# Threeno_DB28_Tx_Rev1.net
KiCad netlist of a schematic drawn in EAGLE
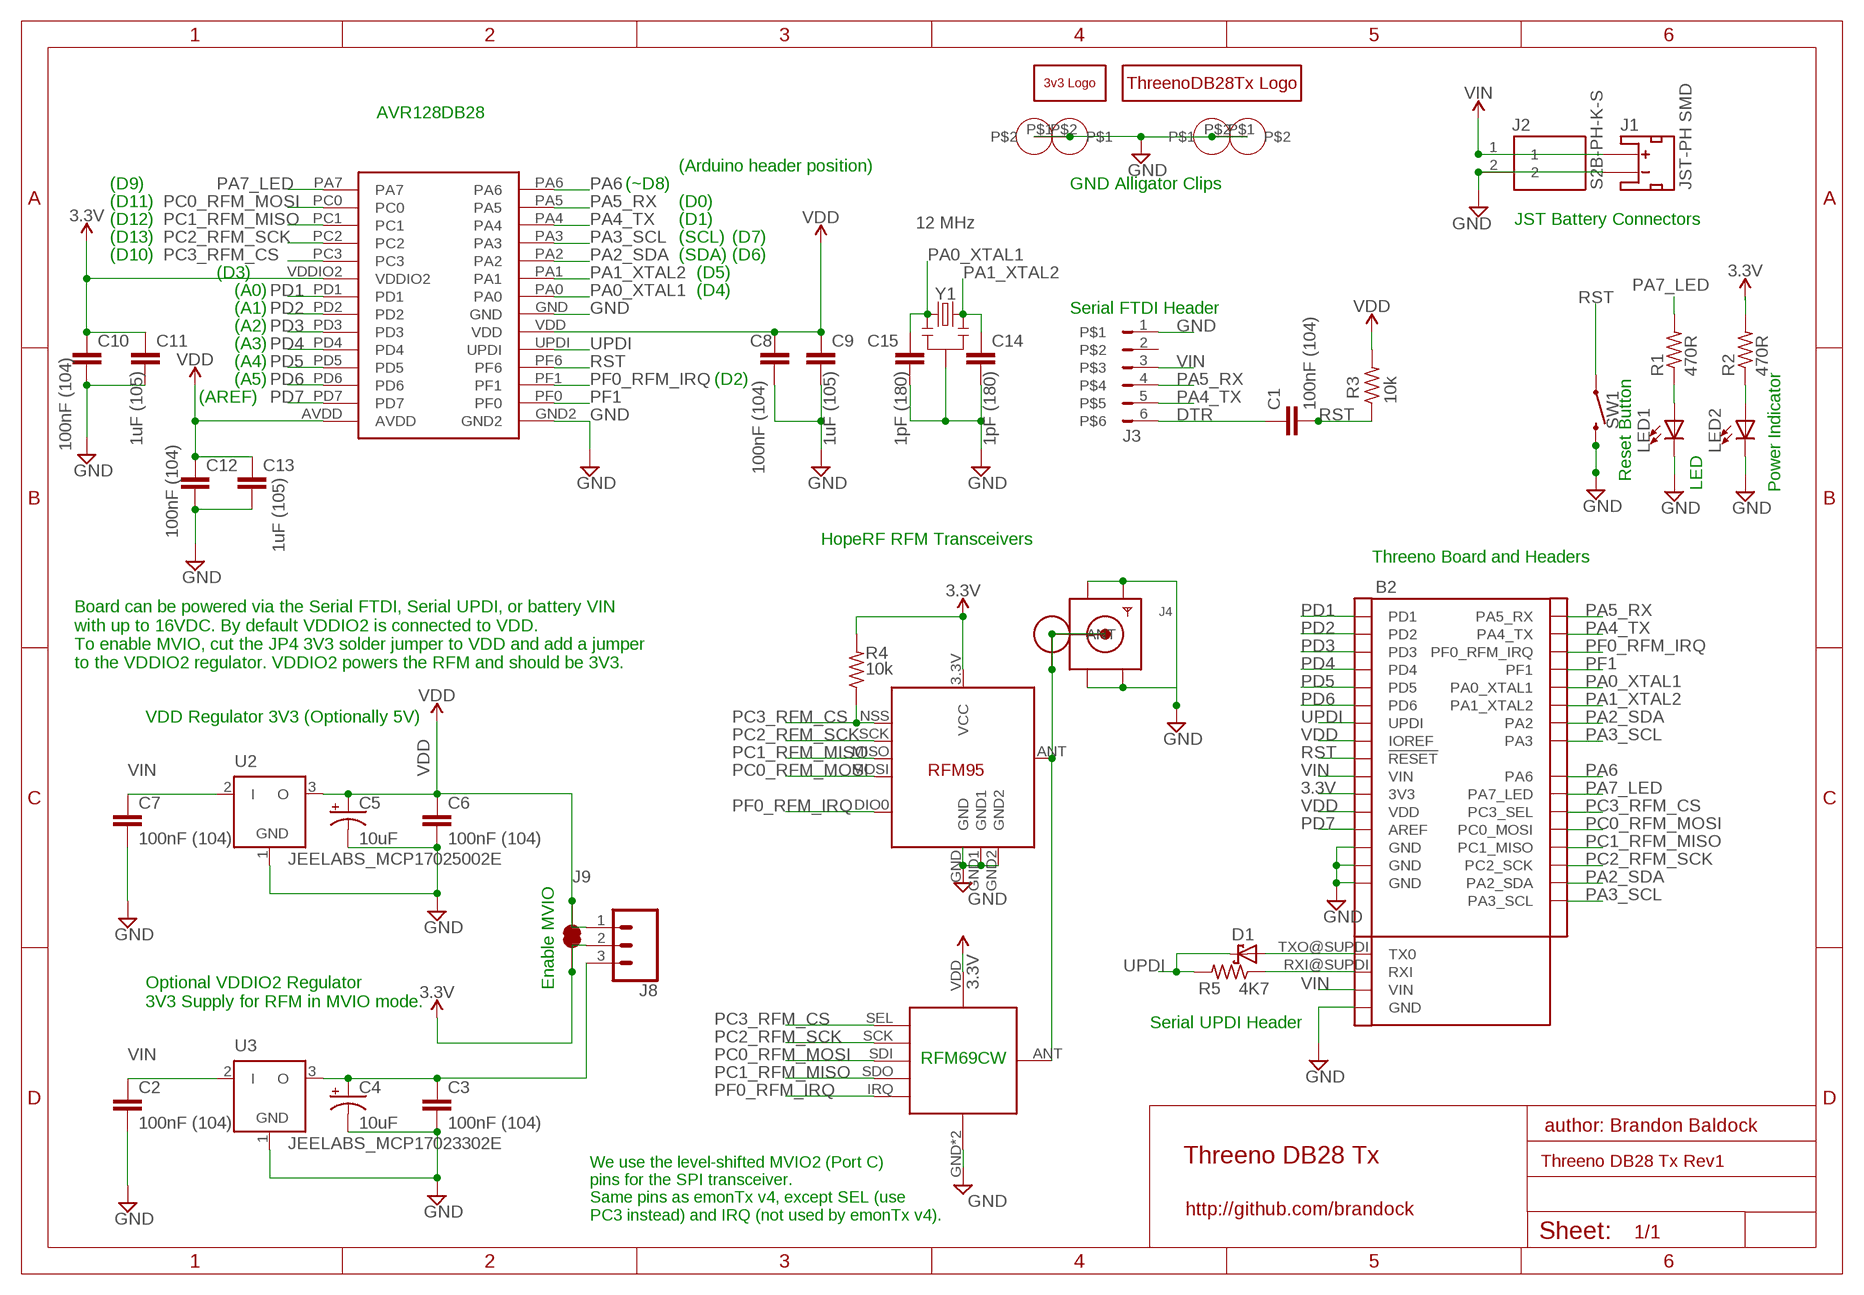
[diagram p0: schematic, sheet 1]

(export (version "E")
  (design (tool "Eeschema 10.0.6"))
  (components
    (comp (ref "B1")
      (value "3VTHREENO_BOTTOM_SILK")
      (footprint "eagle-import:3VTHREENO_BOTTOM_SILK")
      (libsource (lib "eagle-import") (part "3VTHREENO_BOTTOM_SILK"))
    )
    (comp (ref "B2")
      (value "THREENO_DB28_TX_BOARD_V1.1")
      (footprint "eagle-import:THREENO_DB28_TX_BOARD_V1.1")
      (libsource (lib "eagle-import") (part "THREENO_DB28_TX_BOARD_V1.1"))
    )
    (comp (ref "B3")
      (value "THREENO_DB28_TX_LOGO")
      (footprint "eagle-import:THREENO_DB28_TX_LOGO")
      (libsource (lib "eagle-import") (part "THREENO_DB28_TX_LOGO"))
    )
    (comp (ref "C1")
      (value "100nF (104)")
      (footprint "eagle-import:C025-024X044-NO-MIDDLE-SILK")
      (libsource (lib "eagle-import") (part "C-EU025-024X044-NO_MIDDLE_SILK"))
    )
    (comp (ref "C2")
      (value "100nF (104)")
      (footprint "eagle-import:C025-024X044-NO-MIDDLE-SILK")
      (libsource (lib "eagle-import") (part "C-EU025-024X044-NO_MIDDLE_SILK"))
    )
    (comp (ref "C3")
      (value "100nF (104)")
      (footprint "eagle-import:C025-024X044-NO-MIDDLE-SILK")
      (libsource (lib "eagle-import") (part "C-EU025-024X044-NO_MIDDLE_SILK"))
    )
    (comp (ref "C4")
      (value "10uF")
      (footprint "eagle-import:E1,8-4")
      (libsource (lib "eagle-import") (part "CPOL-USE1.8-4"))
    )
    (comp (ref "C5")
      (value "10uF")
      (footprint "eagle-import:E1,8-4")
      (libsource (lib "eagle-import") (part "CPOL-USE1.8-4"))
    )
    (comp (ref "C6")
      (value "100nF (104)")
      (footprint "eagle-import:C025-024X044-NO-MIDDLE-SILK")
      (libsource (lib "eagle-import") (part "C-EU025-024X044-NO_MIDDLE_SILK"))
    )
    (comp (ref "C7")
      (value "100nF (104)")
      (footprint "eagle-import:C025-024X044-NO-MIDDLE-SILK")
      (libsource (lib "eagle-import") (part "C-EU025-024X044-NO_MIDDLE_SILK"))
    )
    (comp (ref "C8")
      (value "100nF (104)")
      (footprint "eagle-import:C025-024X044-NO-MIDDLE-SILK")
      (libsource (lib "eagle-import") (part "C-EU025-024X044-NO_MIDDLE_SILK"))
    )
    (comp (ref "C9")
      (value "1uF (105)")
      (footprint "eagle-import:C025-024X044-NO-MIDDLE-SILK")
      (libsource (lib "eagle-import") (part "C-EU025-024X044-NO_MIDDLE_SILK"))
    )
    (comp (ref "C10")
      (value "100nF (104)")
      (footprint "eagle-import:C025-024X044-NO-MIDDLE-SILK")
      (libsource (lib "eagle-import") (part "C-EU025-024X044-NO_MIDDLE_SILK"))
    )
    (comp (ref "C11")
      (value "1uF (105)")
      (footprint "eagle-import:C025-024X044-NO-MIDDLE-SILK")
      (libsource (lib "eagle-import") (part "C-EU025-024X044-NO_MIDDLE_SILK"))
    )
    (comp (ref "C12")
      (value "100nF (104)")
      (footprint "eagle-import:C025-024X044-NO-MIDDLE-SILK")
      (libsource (lib "eagle-import") (part "C-EU025-024X044-NO_MIDDLE_SILK"))
    )
    (comp (ref "C13")
      (value "1uF (105)")
      (footprint "eagle-import:C025-024X044-NO-MIDDLE-SILK")
      (libsource (lib "eagle-import") (part "C-EU025-024X044-NO_MIDDLE_SILK"))
    )
    (comp (ref "C14")
      (value "1pF (180)")
      (footprint "eagle-import:C025-024X044-NO-MIDDLE-SILK")
      (libsource (lib "eagle-import") (part "C-EU025-024X044-NO_MIDDLE_SILK"))
    )
    (comp (ref "C15")
      (value "1pF (180)")
      (footprint "eagle-import:C025-024X044-NO-MIDDLE-SILK")
      (libsource (lib "eagle-import") (part "C-EU025-024X044-NO_MIDDLE_SILK"))
    )
    (comp (ref "D1")
      (value "DIODE SCHOTTKY 30V 200MA DO35")
      (footprint "eagle-import:DO41-7")
      (libsource (lib "eagle-import") (part "SCHOTTKY-DIODEDO41-7"))
    )
    (comp (ref "J1")
      (value "JST_2MM_MALE")
      (footprint "eagle-import:JST-2-SMD")
      (libsource (lib "eagle-import") (part "JST_2MM_MALE"))
    )
    (comp (ref "J2")
      (value "S2B-PH-K-S")
      (footprint "eagle-import:S2BPHKS")
      (libsource (lib "eagle-import") (part "S2B-PH-K-S"))
    )
    (comp (ref "J3")
      (value "FTDI")
      (footprint "eagle-import:FTDI_ROUND_HEADER_SILK")
      (libsource (lib "eagle-import") (part "FTDI"))
    )
    (comp (ref "J4")
      (value "SMACONNECTOR_EDGE")
      (footprint "eagle-import:SMA_EDGELAUNCH")
      (libsource (lib "eagle-import") (part "SMACONNECTOR_EDGE"))
    )
    (comp (ref "J5")
      (value "RFM12B_ANTENNA")
      (footprint "eagle-import:RFM12B-ANTENNA")
      (libsource (lib "eagle-import") (part "RFM12B_ANTENNA"))
    )
    (comp (ref "J6")
      (value "ALLIGATORCLIP-WIRELOOP")
      (footprint "eagle-import:ALLIGATORCLIP-WIRELOOP")
      (libsource (lib "eagle-import") (part "ALLIGATORCLIP-WIRELOOP"))
    )
    (comp (ref "J7")
      (value "ALLIGATORCLIP-WIRELOOP")
      (footprint "eagle-import:ALLIGATORCLIP-WIRELOOP")
      (libsource (lib "eagle-import") (part "ALLIGATORCLIP-WIRELOOP"))
    )
    (comp (ref "J8")
      (value "455-1750-1-ND")
      (footprint "eagle-import:1X03")
      (libsource (lib "eagle-import") (part "CONN_03"))
    )
    (comp (ref "J9")
      (value "JUMPER-SMT_2_NC_TRACE_24_MIL_NO-SILK")
      (footprint "eagle-import:SMT-JUMPER_2_NC_TRACE_NO-SILK_24_MIL")
      (libsource (lib "eagle-import") (part "JUMPER-SMT_2_NC_TRACE_24_MIL_NO-SILK"))
    )
    (comp (ref "LED1")
      (value "LED-BRANDOCK3MM")
      (footprint "eagle-import:LED3MM-BRANDOCK")
      (libsource (lib "eagle-import") (part "LED-BRANDOCK3MM"))
    )
    (comp (ref "LED2")
      (value "LED-BRANDOCK3MM")
      (footprint "eagle-import:LED3MM-BRANDOCK")
      (libsource (lib "eagle-import") (part "LED-BRANDOCK3MM"))
    )
    (comp (ref "R1")
      (value "470R")
      (footprint "eagle-import:0204_7")
      (libsource (lib "eagle-import") (part "R-US_0204/7"))
    )
    (comp (ref "R2")
      (value "470R")
      (footprint "eagle-import:0204_7")
      (libsource (lib "eagle-import") (part "R-US_0204/7"))
    )
    (comp (ref "R3")
      (value "10k")
      (footprint "eagle-import:0204_7")
      (libsource (lib "eagle-import") (part "R-US_0204/7"))
    )
    (comp (ref "R4")
      (value "10k")
      (footprint "eagle-import:0204_7")
      (libsource (lib "eagle-import") (part "R-US_0204/7"))
    )
    (comp (ref "R5")
      (value "4K7")
      (footprint "eagle-import:0204_7")
      (libsource (lib "eagle-import") (part "R-US_0204/7"))
    )
    (comp (ref "RF1")
      (value "RFM12B_MINPADS")
      (footprint "eagle-import:RFM12B-MINPADS")
      (libsource (lib "eagle-import") (part "RFM12B_MINPADS"))
    )
    (comp (ref "RF2")
      (value "RFM95LONGER")
      (footprint "eagle-import:RFM95_LONGER")
      (libsource (lib "eagle-import") (part "RFM95LONGER"))
    )
    (comp (ref "SW1")
      (value "MOMENTARY-SWITCH-SPST-PTH-6.0MM")
      (footprint "eagle-import:TACTILE_SWITCH_PTH_6.0MM")
      (libsource (lib "eagle-import") (part "MOMENTARY-SWITCH-SPST-PTH-6.0MM"))
    )
    (comp (ref "U1")
      (value "AVR128DB28")
      (footprint "eagle-import:DIL28-3")
      (libsource (lib "eagle-import") (part "AVR128DB28"))
    )
    (comp (ref "U2")
      (value "JEELABS_MCP17025002E")
      (footprint "eagle-import:JEELABS_TO92")
      (libsource (lib "eagle-import") (part "JEELABS_MCP17025002E"))
    )
    (comp (ref "U3")
      (value "JEELABS_MCP17023302E")
      (footprint "eagle-import:JEELABS_TO92")
      (libsource (lib "eagle-import") (part "JEELABS_MCP17023302E"))
    )
    (comp (ref "Y1")
      (value "12 MHz")
      (footprint "eagle-import:HC49US-OR-RESONATOR")
      (libsource (lib "eagle-import") (part "CRYSTAL-OR-RESONATOR"))
    )
  )
  (nets
    (net (code "1") (name "/DTR") (class "Default")
      (node (ref "C1") (pin "1") (pinfunction "1_1") (pintype "passive"))
      (node (ref "J3") (pin "6") (pinfunction "P$6_6") (pintype "bidirectional"))
    )
    (net (code "2") (name "/PA0_XTAL1") (class "Default")
      (node (ref "B2") (pin "PA0") (pinfunction "PA0_XTAL1_PA0") (pintype "bidirectional"))
      (node (ref "C15") (pin "1") (pinfunction "1_1") (pintype "passive"))
      (node (ref "U1") (pin "PA0") (pinfunction "PA0_PA0") (pintype "bidirectional"))
      (node (ref "Y1") (pin "1") (pinfunction "1_1") (pintype "passive"))
    )
    (net (code "3") (name "/PA1_XTAL2") (class "Default")
      (node (ref "B2") (pin "PA1") (pinfunction "PA1_XTAL2_PA1") (pintype "bidirectional"))
      (node (ref "C14") (pin "1") (pinfunction "1_1") (pintype "passive"))
      (node (ref "U1") (pin "PA1") (pinfunction "PA1_PA1") (pintype "bidirectional"))
      (node (ref "Y1") (pin "3") (pinfunction "3_3") (pintype "passive"))
    )
    (net (code "4") (name "/PA2_SDA") (class "Default")
      (node (ref "B2") (pin "PA2") (pinfunction "PA2_PA2") (pintype "bidirectional"))
      (node (ref "B2") (pin "PA2|SDA") (pinfunction "PA2_SDA_PA2|SDA") (pintype "bidirectional"))
      (node (ref "U1") (pin "PA2") (pinfunction "PA2_PA2") (pintype "bidirectional"))
    )
    (net (code "5") (name "/PA3_SCL") (class "Default")
      (node (ref "B2") (pin "PA3") (pinfunction "PA3_PA3") (pintype "bidirectional"))
      (node (ref "B2") (pin "PA3|SCL") (pinfunction "PA3_SCL_PA3|SCL") (pintype "bidirectional"))
      (node (ref "U1") (pin "PA3") (pinfunction "PA3_PA3") (pintype "bidirectional"))
    )
    (net (code "6") (name "/PA4_TX") (class "Default")
      (node (ref "B2") (pin "PA4|TX") (pinfunction "PA4_TX_PA4|TX") (pintype "bidirectional"))
      (node (ref "J3") (pin "5") (pinfunction "P$5_5") (pintype "bidirectional"))
      (node (ref "U1") (pin "PA4") (pinfunction "PA4_PA4") (pintype "bidirectional"))
    )
    (net (code "7") (name "/PA5_RX") (class "Default")
      (node (ref "B2") (pin "PA5|RX") (pinfunction "PA5_RX_PA5|RX") (pintype "bidirectional"))
      (node (ref "J3") (pin "4") (pinfunction "P$4_4") (pintype "bidirectional"))
      (node (ref "U1") (pin "PA5") (pinfunction "PA5_PA5") (pintype "bidirectional"))
    )
    (net (code "8") (name "/PA6") (class "Default")
      (node (ref "B2") (pin "PA6") (pinfunction "PA6_PA6") (pintype "bidirectional"))
      (node (ref "U1") (pin "PA6") (pinfunction "PA6_PA6") (pintype "bidirectional"))
    )
    (net (code "9") (name "/PA7_LED") (class "Default")
      (node (ref "B2") (pin "PA7") (pinfunction "PA7_LED_PA7") (pintype "bidirectional"))
      (node (ref "R1") (pin "2") (pinfunction "2_2") (pintype "passive"))
      (node (ref "U1") (pin "PA7") (pinfunction "PA7_PA7") (pintype "bidirectional"))
    )
    (net (code "10") (name "/PC0_RFM_MOSI") (class "Default")
      (node (ref "B2") (pin "PC0") (pinfunction "PC0_MOSI_PC0") (pintype "bidirectional"))
      (node (ref "RF1") (pin "SDI") (pinfunction "SDI/MOSI_SDI") (pintype "bidirectional"))
      (node (ref "RF2") (pin "MOSI") (pinfunction "MOSI_MOSI") (pintype "output"))
      (node (ref "U1") (pin "PC0") (pinfunction "PC0_PC0") (pintype "bidirectional"))
    )
    (net (code "11") (name "/PC1_RFM_MISO") (class "Default")
      (node (ref "B2") (pin "PC1") (pinfunction "PC1_MISO_PC1") (pintype "bidirectional"))
      (node (ref "RF1") (pin "SDO") (pinfunction "SDO/MISO_SDO") (pintype "bidirectional"))
      (node (ref "RF2") (pin "MISO") (pinfunction "MISO_MISO") (pintype "input"))
      (node (ref "U1") (pin "PC1") (pinfunction "PC1_PC1") (pintype "bidirectional"))
    )
    (net (code "12") (name "/PC2_RFM_SCK") (class "Default")
      (node (ref "B2") (pin "PC2") (pinfunction "PC2_SCK_PC2") (pintype "bidirectional"))
      (node (ref "RF1") (pin "SCK") (pinfunction "SCK_SCK") (pintype "bidirectional"))
      (node (ref "RF2") (pin "SCK") (pinfunction "SCK_SCK") (pintype "input"))
      (node (ref "U1") (pin "PC2") (pinfunction "PC2_PC2") (pintype "bidirectional"))
    )
    (net (code "13") (name "/PC3_RFM_CS") (class "Default")
      (node (ref "B2") (pin "PC3") (pinfunction "PC3_SEL_PC3") (pintype "bidirectional"))
      (node (ref "R4") (pin "1") (pinfunction "1_1") (pintype "passive"))
      (node (ref "RF1") (pin "SEL") (pinfunction "SEL_SEL") (pintype "bidirectional"))
      (node (ref "RF2") (pin "NSS") (pinfunction "SEL_NSS") (pintype "input"))
      (node (ref "U1") (pin "PC3") (pinfunction "PC3_PC3") (pintype "bidirectional"))
    )
    (net (code "14") (name "/PD1") (class "Default")
      (node (ref "B2") (pin "PD1|A0") (pinfunction "PD1_PD1|A0") (pintype "bidirectional"))
      (node (ref "U1") (pin "PD1") (pinfunction "PD1_PD1") (pintype "bidirectional"))
    )
    (net (code "15") (name "/PD2") (class "Default")
      (node (ref "B2") (pin "PD2|A1") (pinfunction "PD2_PD2|A1") (pintype "bidirectional"))
      (node (ref "U1") (pin "PD2") (pinfunction "PD2_PD2") (pintype "bidirectional"))
    )
    (net (code "16") (name "/PD3") (class "Default")
      (node (ref "B2") (pin "PD3|A2") (pinfunction "PD3_PD3|A2") (pintype "bidirectional"))
      (node (ref "U1") (pin "PD3") (pinfunction "PD3_PD3") (pintype "bidirectional"))
    )
    (net (code "17") (name "/PD4") (class "Default")
      (node (ref "B2") (pin "PD4|A3") (pinfunction "PD4_PD4|A3") (pintype "bidirectional"))
      (node (ref "U1") (pin "PD4") (pinfunction "PD4_PD4") (pintype "bidirectional"))
    )
    (net (code "18") (name "/PD5") (class "Default")
      (node (ref "B2") (pin "PD5|A4") (pinfunction "PD5_PD5|A4") (pintype "bidirectional"))
      (node (ref "U1") (pin "PD5") (pinfunction "PD5_PD5") (pintype "bidirectional"))
    )
    (net (code "19") (name "/PD6") (class "Default")
      (node (ref "B2") (pin "PD6|A5") (pinfunction "PD6_PD6|A5") (pintype "bidirectional"))
      (node (ref "U1") (pin "PD6") (pinfunction "PD6_PD6") (pintype "bidirectional"))
    )
    (net (code "20") (name "/PD7") (class "Default")
      (node (ref "B2") (pin "PD7") (pinfunction "AREF_PD7") (pintype "bidirectional"))
      (node (ref "U1") (pin "PD7") (pinfunction "PD7_PD7") (pintype "bidirectional"))
    )
    (net (code "21") (name "/PF0_RFM_IRQ") (class "Default")
      (node (ref "B2") (pin "PF0") (pinfunction "PF0_RFM_IRQ_PF0") (pintype "bidirectional"))
      (node (ref "RF1") (pin "IRQ") (pinfunction "IRQ_IRQ") (pintype "bidirectional"))
      (node (ref "RF2") (pin "DIO0") (pinfunction "DIO0_DIO0") (pintype "open_collector"))
      (node (ref "U1") (pin "PF1") (pinfunction "PF1_PF1") (pintype "bidirectional"))
    )
    (net (code "22") (name "/PF1") (class "Default")
      (node (ref "B2") (pin "PF1") (pinfunction "PF1_PF1") (pintype "bidirectional"))
      (node (ref "U1") (pin "PF0") (pinfunction "PF0_PF0") (pintype "bidirectional"))
    )
    (net (code "23") (name "/RST") (class "Default")
      (node (ref "B2") (pin "RESET@1") (pinfunction "~{RESET}_RESET@1") (pintype "bidirectional"))
      (node (ref "C1") (pin "2") (pinfunction "2_2") (pintype "passive"))
      (node (ref "R3") (pin "1") (pinfunction "1_1") (pintype "passive"))
      (node (ref "SW1") (pin "1") (pinfunction "1_1") (pintype "passive"))
      (node (ref "U1") (pin "PF6") (pinfunction "PF6_PF6") (pintype "bidirectional"))
    )
    (net (code "24") (name "/UPDI") (class "Default")
      (node (ref "B2") (pin "NC") (pinfunction "UPDI_NC") (pintype "bidirectional"))
      (node (ref "D1") (pin "C") (pinfunction "C_C") (pintype "passive"))
      (node (ref "R5") (pin "2") (pinfunction "2_2") (pintype "passive"))
      (node (ref "U1") (pin "UPDI") (pinfunction "UPDI_UPDI") (pintype "bidirectional"))
    )
    (net (code "25") (name "3.3V") (class "Default")
      (node (ref "B2") (pin "3.3V") (pinfunction "3V3_3.3V") (pintype "bidirectional"))
      (node (ref "C10") (pin "1") (pinfunction "1_1") (pintype "passive"))
      (node (ref "C11") (pin "1") (pinfunction "1_1") (pintype "passive"))
      (node (ref "J8") (pin "2") (pinfunction "2_2") (pintype "passive"))
      (node (ref "J9") (pin "2") (pinfunction "2_2") (pintype "passive"))
      (node (ref "R2") (pin "2") (pinfunction "2_2") (pintype "passive"))
      (node (ref "R4") (pin "2") (pinfunction "2_2") (pintype "passive"))
      (node (ref "RF1") (pin "VDD") (pinfunction "VDD_VDD") (pintype "bidirectional"))
      (node (ref "RF2") (pin "3.3V") (pinfunction "VCC_3.3V") (pintype "power_in"))
      (node (ref "U1") (pin "VDDIO2") (pinfunction "VDDIO2_VDDIO2") (pintype "bidirectional"))
    )
    (net (code "26") (name "GND") (class "Default")
      (node (ref "B2") (pin "GND@1") (pinfunction "GND_GND@1") (pintype "bidirectional"))
      (node (ref "B2") (pin "GND@2") (pinfunction "GND_GND@2") (pintype "bidirectional"))
      (node (ref "B2") (pin "GND@3") (pinfunction "GND_GND@3") (pintype "bidirectional"))
      (node (ref "B2") (pin "GND@SUPDI") (pinfunction "GND_GND@SUPDI") (pintype "bidirectional"))
      (node (ref "C10") (pin "2") (pinfunction "2_2") (pintype "passive"))
      (node (ref "C11") (pin "2") (pinfunction "2_2") (pintype "passive"))
      (node (ref "C12") (pin "2") (pinfunction "2_2") (pintype "passive"))
      (node (ref "C13") (pin "2") (pinfunction "2_2") (pintype "passive"))
      (node (ref "C14") (pin "2") (pinfunction "2_2") (pintype "passive"))
      (node (ref "C15") (pin "2") (pinfunction "2_2") (pintype "passive"))
      (node (ref "C2") (pin "2") (pinfunction "2_2") (pintype "passive"))
      (node (ref "C3") (pin "2") (pinfunction "2_2") (pintype "passive"))
      (node (ref "C4") (pin "-") (pinfunction "-_-") (pintype "passive"))
      (node (ref "C5") (pin "-") (pinfunction "-_-") (pintype "passive"))
      (node (ref "C6") (pin "2") (pinfunction "2_2") (pintype "passive"))
      (node (ref "C7") (pin "2") (pinfunction "2_2") (pintype "passive"))
      (node (ref "C8") (pin "2") (pinfunction "2_2") (pintype "passive"))
      (node (ref "C9") (pin "2") (pinfunction "2_2") (pintype "passive"))
      (node (ref "J1") (pin "1") (pinfunction "-_1") (pintype "bidirectional"))
      (node (ref "J2") (pin "2") (pinfunction "2_2") (pintype "bidirectional"))
      (node (ref "J3") (pin "1") (pinfunction "P$1_1") (pintype "bidirectional"))
      (node (ref "J4") (pin "GND@1") (pinfunction "GND4_GND@1") (pintype "power_in"))
      (node (ref "J4") (pin "GND@2") (pinfunction "GND3_GND@2") (pintype "power_in"))
      (node (ref "J4") (pin "GND@3") (pinfunction "GND2_GND@3") (pintype "power_in"))
      (node (ref "J4") (pin "GND@4") (pinfunction "GND1_GND@4") (pintype "power_in"))
      (node (ref "J6") (pin "P$1") (pinfunction "P$1_P$1") (pintype "bidirectional"))
      (node (ref "J6") (pin "P$2") (pinfunction "P$2_P$2") (pintype "bidirectional"))
      (node (ref "J7") (pin "P$1") (pinfunction "P$1_P$1") (pintype "bidirectional"))
      (node (ref "J7") (pin "P$2") (pinfunction "P$2_P$2") (pintype "bidirectional"))
      (node (ref "LED1") (pin "K") (pinfunction "C_K") (pintype "passive"))
      (node (ref "LED2") (pin "K") (pinfunction "C_K") (pintype "passive"))
      (node (ref "RF1") (pin "GND") (pinfunction "GND_GND") (pintype "bidirectional"))
      (node (ref "RF1") (pin "GND2") (pinfunction "GND_GND2") (pintype "bidirectional"))
      (node (ref "RF2") (pin "GND") (pinfunction "GND_GND") (pintype "power_in"))
      (node (ref "RF2") (pin "GND1") (pinfunction "GND1_GND1") (pintype "power_in"))
      (node (ref "RF2") (pin "GND2") (pinfunction "GND2_GND2") (pintype "power_in"))
      (node (ref "SW1") (pin "3") (pinfunction "2_3") (pintype "passive"))
      (node (ref "U1") (pin "GND") (pinfunction "GND_GND") (pintype "bidirectional"))
      (node (ref "U1") (pin "GND2") (pinfunction "GND2_GND2") (pintype "bidirectional"))
      (node (ref "U2") (pin "1") (pinfunction "GND_1") (pintype "power_in"))
      (node (ref "U3") (pin "1") (pinfunction "GND_1") (pintype "power_in"))
      (node (ref "Y1") (pin "2") (pinfunction "2_2") (pintype "passive"))
    )
    (net (code "27") (name "Net-(B2-RXI)") (class "Default")
      (node (ref "B2") (pin "RXI@SUPDI") (pinfunction "RXI_RXI@SUPDI") (pintype "bidirectional"))
      (node (ref "R5") (pin "1") (pinfunction "1_1") (pintype "passive"))
    )
    (net (code "28") (name "Net-(B2-TX0)") (class "Default")
      (node (ref "B2") (pin "TXO@SUPDI") (pinfunction "TX0_TXO@SUPDI") (pintype "bidirectional"))
      (node (ref "D1") (pin "A") (pinfunction "A_A") (pintype "passive"))
    )
    (net (code "29") (name "Net-(J4-ANT)") (class "Default")
      (node (ref "J4") (pin "P") (pinfunction "ANT_P") (pintype "bidirectional"))
      (node (ref "J5") (pin "P$1") (pinfunction "1_P$1") (pintype "bidirectional"))
      (node (ref "RF1") (pin "ANT") (pinfunction "ANT_ANT") (pintype "bidirectional"))
      (node (ref "RF2") (pin "ANT") (pinfunction "ANT_ANT") (pintype "passive"))
    )
    (net (code "30") (name "Net-(LED1-PadA)") (class "Default")
      (node (ref "LED1") (pin "A") (pinfunction "A_A") (pintype "passive"))
      (node (ref "R1") (pin "1") (pinfunction "1_1") (pintype "passive"))
    )
    (net (code "31") (name "Net-(LED2-PadA)") (class "Default")
      (node (ref "LED2") (pin "A") (pinfunction "A_A") (pintype "passive"))
      (node (ref "R2") (pin "1") (pinfunction "1_1") (pintype "passive"))
    )
    (net (code "32") (name "Net-(U3-O)") (class "Default")
      (node (ref "C3") (pin "1") (pinfunction "1_1") (pintype "passive"))
      (node (ref "C4") (pin "+") (pinfunction "+_+") (pintype "passive"))
      (node (ref "J8") (pin "3") (pinfunction "3_3") (pintype "passive"))
      (node (ref "U3") (pin "3") (pinfunction "O_3") (pintype "input"))
    )
    (net (code "33") (name "VDD") (class "Default")
      (node (ref "B2") (pin "VDD") (pinfunction "VDD_VDD") (pintype "bidirectional"))
      (node (ref "B2") (pin "VDD|IOREF") (pinfunction "IOREF_VDD|IOREF") (pintype "bidirectional"))
      (node (ref "C12") (pin "1") (pinfunction "1_1") (pintype "passive"))
      (node (ref "C13") (pin "1") (pinfunction "1_1") (pintype "passive"))
      (node (ref "C5") (pin "+") (pinfunction "+_+") (pintype "passive"))
      (node (ref "C6") (pin "1") (pinfunction "1_1") (pintype "passive"))
      (node (ref "C8") (pin "1") (pinfunction "1_1") (pintype "passive"))
      (node (ref "C9") (pin "1") (pinfunction "1_1") (pintype "passive"))
      (node (ref "J8") (pin "1") (pinfunction "1_1") (pintype "passive"))
      (node (ref "J9") (pin "1") (pinfunction "1_1") (pintype "passive"))
      (node (ref "R3") (pin "2") (pinfunction "2_2") (pintype "passive"))
      (node (ref "U1") (pin "AVDD") (pinfunction "AVDD_AVDD") (pintype "bidirectional"))
      (node (ref "U1") (pin "VDD") (pinfunction "VDD_VDD") (pintype "bidirectional"))
      (node (ref "U2") (pin "3") (pinfunction "O_3") (pintype "input"))
    )
    (net (code "34") (name "VIN") (class "Default")
      (node (ref "B2") (pin "VIN") (pinfunction "VIN_VIN") (pintype "bidirectional"))
      (node (ref "B2") (pin "VIN@SUPDI") (pinfunction "VIN_VIN@SUPDI") (pintype "bidirectional"))
      (node (ref "C2") (pin "1") (pinfunction "1_1") (pintype "passive"))
      (node (ref "C7") (pin "1") (pinfunction "1_1") (pintype "passive"))
      (node (ref "J1") (pin "2") (pinfunction "+_2") (pintype "bidirectional"))
      (node (ref "J2") (pin "1") (pinfunction "1_1") (pintype "bidirectional"))
      (node (ref "J3") (pin "3") (pinfunction "P$3_3") (pintype "bidirectional"))
      (node (ref "U2") (pin "2") (pinfunction "I_2") (pintype "input"))
      (node (ref "U3") (pin "2") (pinfunction "I_2") (pintype "input"))
    )
    (net (code "35") (name "unconnected-(J1-PAD1-PadNC1)") (class "Default")
      (node (ref "J1") (pin "NC1") (pinfunction "PAD1_NC1") (pintype "bidirectional"))
    )
    (net (code "36") (name "unconnected-(J1-PAD2-PadNC2)") (class "Default")
      (node (ref "J1") (pin "NC2") (pinfunction "PAD2_NC2") (pintype "bidirectional"))
    )
    (net (code "37") (name "unconnected-(J3-P$2-Pad2)") (class "Default")
      (node (ref "J3") (pin "2") (pinfunction "P$2_2") (pintype "bidirectional"))
    )
  )
)
